# DXP_LCD12864.net
KiCad netlist of a schematic drawn in Altium Designer
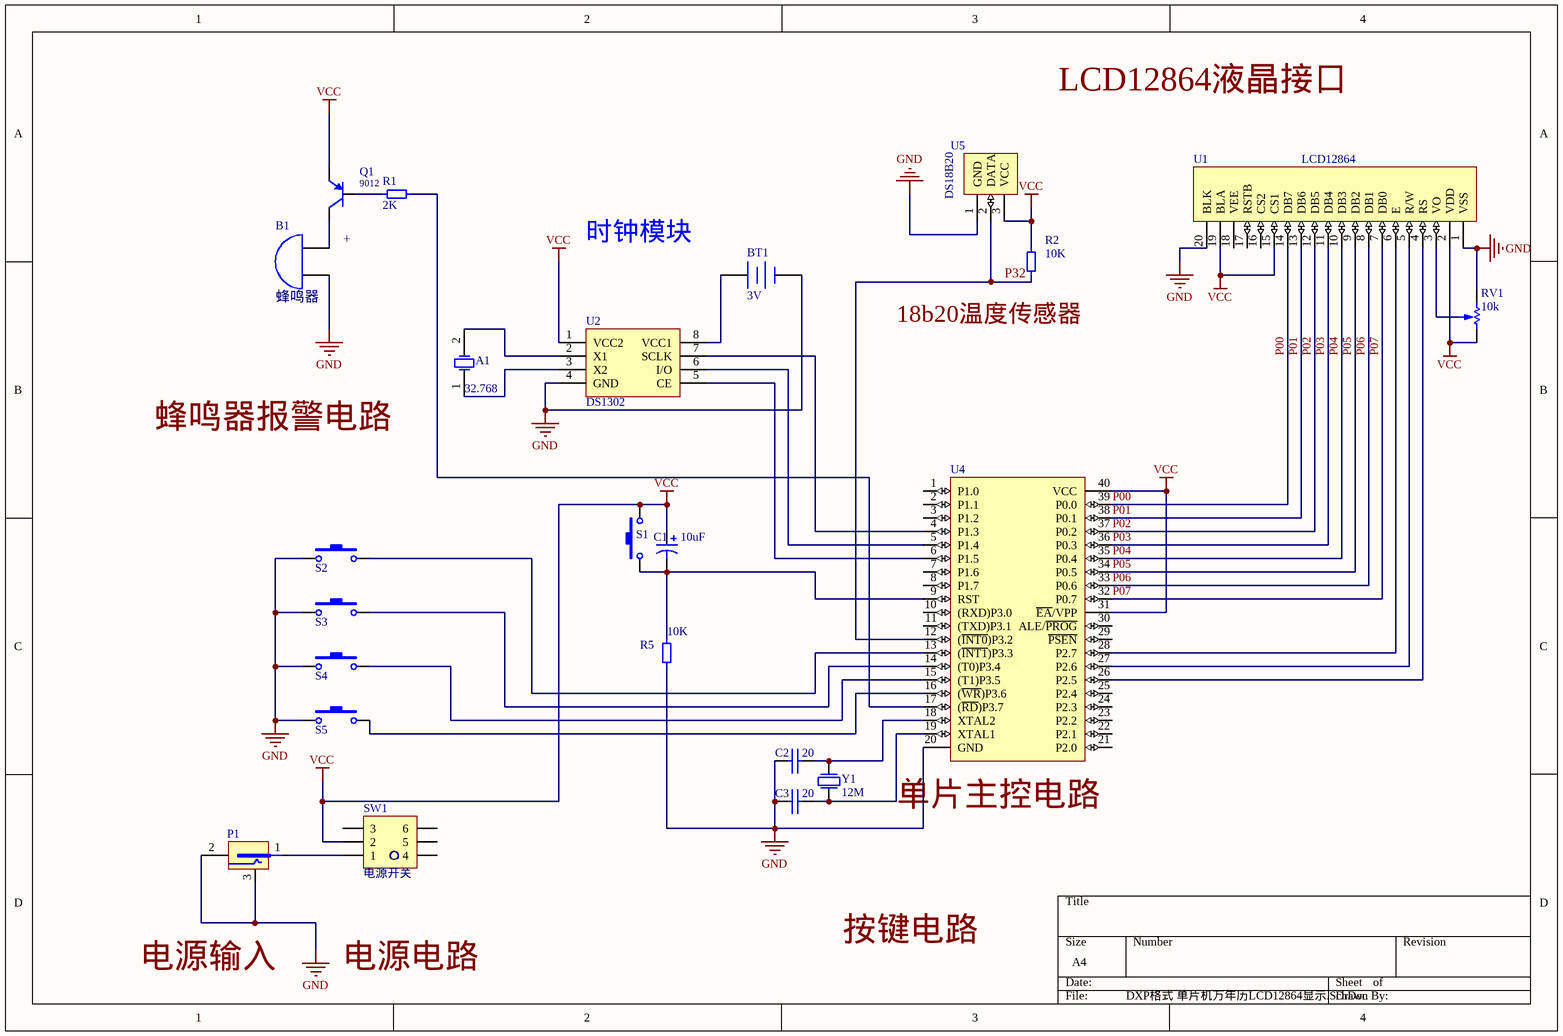
[diagram p0: DXP格式 单片机万年历LCD12864显示.SchDoc]

(export (version "E")
  (design (tool "Eeschema 10.0.6"))
  (components
    (comp (ref "A1") (value "32.768") (footprint "HDR1X2") (libsource (lib "实用原理图库") (part "XTA")))
    (comp (ref "B1")
      (value "蜂鸣器")
      (footprint "Bett")
      (description "Bell")
      (libsource (lib "实验板原理图") (part "BELL"))
    )
    (comp (ref "BT1")
      (value "3V")
      (footprint "BATT")
      (description "Multicell Battery")
      (fields (field (name "PUBLISHER") "Altium Limited"))
      (libsource (lib "Miscellaneous Devices") (part "Battery"))
    )
    (comp (ref "C1")
      (value "10uF")
      (footprint "C_10")
      (description "Polarized Capacitor (Radial)")
      (fields (field (name "PUBLISHER") "Altium Limited"))
      (libsource (lib "简易动环监控系统") (part "Cap Pol1"))
    )
    (comp (ref "C2")
      (value "20")
      (footprint "CAP5")
      (description "电容")
      (libsource (lib "C8051F020最小2") (part "CAP"))
    )
    (comp (ref "C3")
      (value "20")
      (footprint "CAP5")
      (description "电容")
      (libsource (lib "C8051F020最小2") (part "CAP"))
    )
    (comp (ref "P1") (value "电源输入") (footprint "DC2.1") (libsource (lib "我自己的") (part "POWER")))
    (comp (ref "Q1")
      (value "9012")
      (footprint "s三极管直插")
      (description "PNP General Purpose Amplifier")
      (fields (field (name "PUBLISHER") "Altium Limited"))
      (libsource (lib "实验板原理图") (part "2N3906"))
    )
    (comp (ref "R1") (value "2K") (footprint "AXIAL0.3") (libsource (lib "C8051F020最小2") (part "RES2")))
    (comp (ref "R2") (value "10K") (footprint "AXIAL0.3") (libsource (lib "C8051F020最小2") (part "RES2")))
    (comp (ref "R5") (value "10K") (footprint "res400mil") (libsource (lib "C8051F020最小2") (part "RES2")))
    (comp (ref "RV1")
      (value "10k")
      (footprint "可调电阻器")
      (description "可变电阻")
      (fields (field (name "Comment") "R"))
      (libsource (lib "项目电源") (part "R"))
    )
    (comp (ref "S1")
      (value "SW-PB")
      (footprint "key")
      (description "Switch")
      (fields (field (name "PUBLISHER") "Altium Limited"))
      (libsource (lib "实验板原理图") (part "SW-PB"))
    )
    (comp (ref "S2")
      (value "SW-PB")
      (footprint "key")
      (description "Switch")
      (fields (field (name "PUBLISHER") "Altium Limited"))
      (libsource (lib "实验板原理图") (part "SW-PB"))
    )
    (comp (ref "S3")
      (value "SW-PB")
      (footprint "key")
      (description "Switch")
      (fields (field (name "PUBLISHER") "Altium Limited"))
      (libsource (lib "实验板原理图") (part "SW-PB"))
    )
    (comp (ref "S4")
      (value "SW-PB")
      (footprint "key")
      (description "Switch")
      (fields (field (name "PUBLISHER") "Altium Limited"))
      (libsource (lib "实验板原理图") (part "SW-PB"))
    )
    (comp (ref "S5")
      (value "SW-PB")
      (footprint "key")
      (description "Switch")
      (fields (field (name "PUBLISHER") "Altium Limited"))
      (libsource (lib "实验板原理图") (part "SW-PB"))
    )
    (comp (ref "SW1") (value "电源开关") (footprint "sw_自锁 1") (libsource (lib "我自己的") (part "SW1")))
    (comp (ref "U1") (value "LCD12864") (footprint "SIP20") (libsource (lib "我自己的") (part "LCD12864_1")))
    (comp (ref "U2") (value "DS1302") (footprint "DIP8") (libsource (lib "实用原理图库") (part "DS1302")))
    (comp (ref "U4") (value "STC89C52") (footprint "DIP40 - 做板") (libsource (lib "实验板原理图") (part "U1")))
    (comp (ref "U5") (value "DS18B20") (footprint "18B20") (libsource (lib "实验板原理图") (part "DS18B20")))
    (comp (ref "Y1")
      (value "12M")
      (footprint "XTAL")
      (description "Crystal Oscillator")
      (libsource (lib "C8051F020最小2") (part "16M"))
    )
  )
  (nets
    (net (code "3") (name "/P00") (class "Default")
      (node (ref "U1") (pin "14") (pinfunction "DB7_14") (pintype "bidirectional"))
      (node (ref "U4") (pin "39") (pinfunction "P0.0_39") (pintype "bidirectional"))
    )
    (net (code "4") (name "/P01") (class "Default")
      (node (ref "U1") (pin "13") (pinfunction "DB6_13") (pintype "bidirectional"))
      (node (ref "U4") (pin "38") (pinfunction "P0.1_38") (pintype "bidirectional"))
    )
    (net (code "5") (name "/P02") (class "Default")
      (node (ref "U1") (pin "12") (pinfunction "DB5_12") (pintype "bidirectional"))
      (node (ref "U4") (pin "37") (pinfunction "P0.2_37") (pintype "bidirectional"))
    )
    (net (code "6") (name "/P03") (class "Default")
      (node (ref "U1") (pin "11") (pinfunction "DB4_11") (pintype "bidirectional"))
      (node (ref "U4") (pin "36") (pinfunction "P0.3_36") (pintype "bidirectional"))
    )
    (net (code "7") (name "/P04") (class "Default")
      (node (ref "U1") (pin "10") (pinfunction "DB3_10") (pintype "bidirectional"))
      (node (ref "U4") (pin "35") (pinfunction "P0.4_35") (pintype "bidirectional"))
    )
    (net (code "8") (name "/P05") (class "Default")
      (node (ref "U1") (pin "9") (pinfunction "DB2_9") (pintype "bidirectional"))
      (node (ref "U4") (pin "34") (pinfunction "P0.5_34") (pintype "bidirectional"))
    )
    (net (code "9") (name "/P06") (class "Default")
      (node (ref "U1") (pin "8") (pinfunction "DB1_8") (pintype "bidirectional"))
      (node (ref "U4") (pin "33") (pinfunction "P0.6_33") (pintype "bidirectional"))
    )
    (net (code "10") (name "/P07") (class "Default")
      (node (ref "U1") (pin "7") (pinfunction "DB0_7") (pintype "bidirectional"))
      (node (ref "U4") (pin "32") (pinfunction "P0.7_32") (pintype "bidirectional"))
    )
    (net (code "11") (name "/P32") (class "Default")
      (node (ref "R2") (pin "1") (pinfunction "1_1") (pintype "passive"))
      (node (ref "U4") (pin "12") (pinfunction "(~{INT0})P3.2_12") (pintype "bidirectional"))
      (node (ref "U5") (pin "2") (pinfunction "DATA_2") (pintype "bidirectional"))
    )
    (net (code "17") (name "GND") (class "Default")
      (node (ref "B1") (pin "2") (pinfunction "B_2") (pintype "passive"))
      (node (ref "BT1") (pin "2") (pinfunction "-_2") (pintype "passive"))
      (node (ref "C2") (pin "1") (pinfunction "1_1") (pintype "passive"))
      (node (ref "C3") (pin "1") (pinfunction "1_1") (pintype "passive"))
      (node (ref "P1") (pin "2") (pintype "passive"))
      (node (ref "P1") (pin "3") (pintype "passive"))
      (node (ref "R5") (pin "1") (pinfunction "1_1") (pintype "passive"))
      (node (ref "RV1") (pin "3") (pinfunction "3_3") (pintype "passive"))
      (node (ref "S2") (pin "1") (pinfunction "1_1") (pintype "passive"))
      (node (ref "S3") (pin "1") (pinfunction "1_1") (pintype "passive"))
      (node (ref "S4") (pin "1") (pinfunction "1_1") (pintype "passive"))
      (node (ref "S5") (pin "1") (pinfunction "1_1") (pintype "passive"))
      (node (ref "U1") (pin "1") (pinfunction "VSS_1") (pintype "power_in"))
      (node (ref "U1") (pin "20") (pinfunction "BLK_20") (pintype "passive"))
      (node (ref "U2") (pin "4") (pinfunction "GND_4") (pintype "passive"))
      (node (ref "U4") (pin "20") (pinfunction "GND_20") (pintype "power_in"))
      (node (ref "U5") (pin "1") (pinfunction "GND_1") (pintype "power_in"))
    )
    (net (code "18") (name "Net-(A1-OSC1)") (class "Default")
      (node (ref "A1") (pin "1") (pinfunction "OSC1_1") (pintype "passive"))
      (node (ref "U2") (pin "3") (pinfunction "X2_3") (pintype "passive"))
    )
    (net (code "19") (name "Net-(A1-OSC2)") (class "Default")
      (node (ref "A1") (pin "2") (pinfunction "OSC2_2") (pintype "passive"))
      (node (ref "U2") (pin "2") (pinfunction "X1_2") (pintype "passive"))
    )
    (net (code "20") (name "Net-(B1-A)") (class "Default")
      (node (ref "B1") (pin "1") (pinfunction "A_1") (pintype "passive"))
      (node (ref "Q1") (pin "3") (pinfunction "C_3") (pintype "passive"))
    )
    (net (code "21") (name "Net-(BT1-+)") (class "Default")
      (node (ref "BT1") (pin "1") (pinfunction "+_1") (pintype "passive"))
      (node (ref "U2") (pin "8") (pinfunction "VCC1_8") (pintype "passive"))
    )
    (net (code "22") (name "Net-(P1-Pad1)") (class "Default")
      (node (ref "P1") (pin "1") (pintype "passive"))
      (node (ref "SW1") (pin "1") (pinfunction "1_1") (pintype "passive"))
    )
    (net (code "23") (name "Net-(Q1-B)") (class "Default")
      (node (ref "Q1") (pin "2") (pinfunction "B_2") (pintype "passive"))
      (node (ref "R1") (pin "1") (pinfunction "1_1") (pintype "passive"))
    )
    (net (code "24") (name "Net-(U1-E)") (class "Default")
      (node (ref "U1") (pin "6") (pinfunction "E_6") (pintype "bidirectional"))
      (node (ref "U4") (pin "28") (pinfunction "P2.7_28") (pintype "bidirectional"))
    )
    (net (code "25") (name "Net-(U1-RS)") (class "Default")
      (node (ref "U1") (pin "4") (pinfunction "RS_4") (pintype "bidirectional"))
      (node (ref "U4") (pin "26") (pinfunction "P2.5_26") (pintype "bidirectional"))
    )
    (net (code "26") (name "Net-(U1-R{slash}W)") (class "Default")
      (node (ref "U1") (pin "5") (pinfunction "R/W_5") (pintype "bidirectional"))
      (node (ref "U4") (pin "27") (pinfunction "P2.6_27") (pintype "bidirectional"))
    )
    (net (code "27") (name "Net-(U1-VO)") (class "Default")
      (node (ref "RV1") (pin "2") (pinfunction "2_2") (pintype "passive"))
      (node (ref "U1") (pin "3") (pinfunction "VO_3") (pintype "bidirectional"))
    )
    (net (code "28") (name "Net-(U2-CE)") (class "Default")
      (node (ref "U2") (pin "5") (pinfunction "CE_5") (pintype "passive"))
      (node (ref "U4") (pin "6") (pinfunction "P1.5_6") (pintype "bidirectional"))
    )
    (net (code "29") (name "Net-(U2-I{slash}O)") (class "Default")
      (node (ref "U2") (pin "6") (pinfunction "I/O_6") (pintype "passive"))
      (node (ref "U4") (pin "5") (pinfunction "P1.4_5") (pintype "bidirectional"))
    )
    (net (code "30") (name "Net-(U2-SCLK)") (class "Default")
      (node (ref "U2") (pin "7") (pinfunction "SCLK_7") (pintype "passive"))
      (node (ref "U4") (pin "4") (pinfunction "P1.3_4") (pintype "bidirectional"))
    )
    (net (code "31") (name "Net-(U4-(T0)P3.4)") (class "Default")
      (node (ref "S3") (pin "2") (pinfunction "2_2") (pintype "passive"))
      (node (ref "U4") (pin "14") (pinfunction "(T0)P3.4_14") (pintype "bidirectional"))
    )
    (net (code "32") (name "Net-(U4-(T1)P3.5)") (class "Default")
      (node (ref "S4") (pin "2") (pinfunction "2_2") (pintype "passive"))
      (node (ref "U4") (pin "15") (pinfunction "(T1)P3.5_15") (pintype "bidirectional"))
    )
    (net (code "33") (name "Net-(U4-(~{INT1})P3.3)") (class "Default")
      (node (ref "S2") (pin "2") (pinfunction "2_2") (pintype "passive"))
      (node (ref "U4") (pin "13") (pinfunction "(~{INT1})P3.3_13") (pintype "bidirectional"))
    )
    (net (code "34") (name "Net-(U4-(~{RD})P3.7)") (class "Default")
      (node (ref "R1") (pin "2") (pinfunction "2_2") (pintype "passive"))
      (node (ref "U4") (pin "17") (pinfunction "(~{RD})P3.7_17") (pintype "bidirectional"))
    )
    (net (code "35") (name "Net-(U4-(~{WR})P3.6)") (class "Default")
      (node (ref "S5") (pin "2") (pinfunction "2_2") (pintype "passive"))
      (node (ref "U4") (pin "16") (pinfunction "(~{WR})P3.6_16") (pintype "bidirectional"))
    )
    (net (code "36") (name "Net-(U4-RST)") (class "Default")
      (node (ref "C1") (pin "2") (pinfunction "2_2") (pintype "passive"))
      (node (ref "R5") (pin "2") (pinfunction "2_2") (pintype "passive"))
      (node (ref "S1") (pin "1") (pinfunction "1_1") (pintype "passive"))
      (node (ref "U4") (pin "9") (pinfunction "RST_9") (pintype "bidirectional"))
    )
    (net (code "37") (name "Net-(U4-XTAL1)") (class "Default")
      (node (ref "C3") (pin "2") (pinfunction "2_2") (pintype "passive"))
      (node (ref "U4") (pin "19") (pinfunction "XTAL1_19") (pintype "bidirectional"))
      (node (ref "Y1") (pin "2") (pinfunction "P2_2") (pintype "passive"))
    )
    (net (code "38") (name "Net-(U4-XTAL2)") (class "Default")
      (node (ref "C2") (pin "2") (pinfunction "2_2") (pintype "passive"))
      (node (ref "U4") (pin "18") (pinfunction "XTAL2_18") (pintype "bidirectional"))
      (node (ref "Y1") (pin "1") (pinfunction "P1_1") (pintype "passive"))
    )
    (net (code "39") (name "VCC") (class "Default")
      (node (ref "C1") (pin "1") (pinfunction "1_1") (pintype "passive"))
      (node (ref "Q1") (pin "1") (pinfunction "E_1") (pintype "passive"))
      (node (ref "R2") (pin "2") (pinfunction "2_2") (pintype "passive"))
      (node (ref "RV1") (pin "1") (pinfunction "1_1") (pintype "passive"))
      (node (ref "S1") (pin "2") (pinfunction "2_2") (pintype "passive"))
      (node (ref "SW1") (pin "2") (pinfunction "2_2") (pintype "passive"))
      (node (ref "U1") (pin "15") (pinfunction "CS1_15") (pintype "bidirectional"))
      (node (ref "U1") (pin "19") (pinfunction "BLA_19") (pintype "passive"))
      (node (ref "U1") (pin "2") (pinfunction "VDD_2") (pintype "power_in"))
      (node (ref "U2") (pin "1") (pinfunction "VCC2_1") (pintype "passive"))
      (node (ref "U4") (pin "31") (pinfunction "~{EA}/VPP_31") (pintype "power_in"))
      (node (ref "U4") (pin "40") (pinfunction "VCC_40") (pintype "power_in"))
      (node (ref "U5") (pin "3") (pinfunction "VCC_3") (pintype "power_in"))
    )
    (net (code "40") (name "unconnected-(SW1-Pad3)") (class "Default")
      (node (ref "SW1") (pin "3") (pinfunction "3_3") (pintype "passive"))
    )
    (net (code "41") (name "unconnected-(SW1-Pad4)") (class "Default")
      (node (ref "SW1") (pin "4") (pinfunction "4_4") (pintype "passive"))
    )
    (net (code "42") (name "unconnected-(SW1-Pad5)") (class "Default")
      (node (ref "SW1") (pin "5") (pinfunction "5_5") (pintype "passive"))
    )
    (net (code "43") (name "unconnected-(SW1-Pad6)") (class "Default")
      (node (ref "SW1") (pin "6") (pinfunction "6_6") (pintype "passive"))
    )
    (net (code "44") (name "unconnected-(U1-CS2-Pad16)") (class "Default")
      (node (ref "U1") (pin "16") (pinfunction "CS2_16") (pintype "bidirectional"))
    )
    (net (code "45") (name "unconnected-(U1-RSTB-Pad17)") (class "Default")
      (node (ref "U1") (pin "17") (pinfunction "RSTB_17") (pintype "bidirectional"))
    )
    (net (code "46") (name "unconnected-(U1-VEE-Pad18)") (class "Default")
      (node (ref "U1") (pin "18") (pinfunction "VEE_18") (pintype "power_in"))
    )
    (net (code "47") (name "unconnected-(U4-(RXD)P3.0-Pad10)") (class "Default")
      (node (ref "U4") (pin "10") (pinfunction "(RXD)P3.0_10") (pintype "bidirectional"))
    )
    (net (code "48") (name "unconnected-(U4-(TXD)P3.1-Pad11)") (class "Default")
      (node (ref "U4") (pin "11") (pinfunction "(TXD)P3.1_11") (pintype "bidirectional"))
    )
    (net (code "49") (name "unconnected-(U4-ALE{slash}~{PROG}-Pad30)") (class "Default")
      (node (ref "U4") (pin "30") (pinfunction "ALE/~{PROG}_30") (pintype "bidirectional"))
    )
    (net (code "50") (name "unconnected-(U4-P1.0-Pad1)") (class "Default")
      (node (ref "U4") (pin "1") (pinfunction "P1.0_1") (pintype "bidirectional"))
    )
    (net (code "51") (name "unconnected-(U4-P1.1-Pad2)") (class "Default")
      (node (ref "U4") (pin "2") (pinfunction "P1.1_2") (pintype "bidirectional"))
    )
    (net (code "52") (name "unconnected-(U4-P1.2-Pad3)") (class "Default")
      (node (ref "U4") (pin "3") (pinfunction "P1.2_3") (pintype "bidirectional"))
    )
    (net (code "53") (name "unconnected-(U4-P1.6-Pad7)") (class "Default")
      (node (ref "U4") (pin "7") (pinfunction "P1.6_7") (pintype "bidirectional"))
    )
    (net (code "54") (name "unconnected-(U4-P1.7-Pad8)") (class "Default")
      (node (ref "U4") (pin "8") (pinfunction "P1.7_8") (pintype "bidirectional"))
    )
    (net (code "55") (name "unconnected-(U4-P2.0-Pad21)") (class "Default")
      (node (ref "U4") (pin "21") (pinfunction "P2.0_21") (pintype "bidirectional"))
    )
    (net (code "56") (name "unconnected-(U4-P2.1-Pad22)") (class "Default")
      (node (ref "U4") (pin "22") (pinfunction "P2.1_22") (pintype "bidirectional"))
    )
    (net (code "57") (name "unconnected-(U4-P2.2-Pad23)") (class "Default")
      (node (ref "U4") (pin "23") (pinfunction "P2.2_23") (pintype "bidirectional"))
    )
    (net (code "58") (name "unconnected-(U4-P2.3-Pad24)") (class "Default")
      (node (ref "U4") (pin "24") (pinfunction "P2.3_24") (pintype "bidirectional"))
    )
    (net (code "59") (name "unconnected-(U4-P2.4-Pad25)") (class "Default")
      (node (ref "U4") (pin "25") (pinfunction "P2.4_25") (pintype "bidirectional"))
    )
    (net (code "60") (name "unconnected-(U4-~{PSEN}-Pad29)") (class "Default")
      (node (ref "U4") (pin "29") (pinfunction "~{PSEN}_29") (pintype "bidirectional"))
    )
  )
)
